# topboard-v1.net
KiCad netlist of a schematic drawn in EAGLE
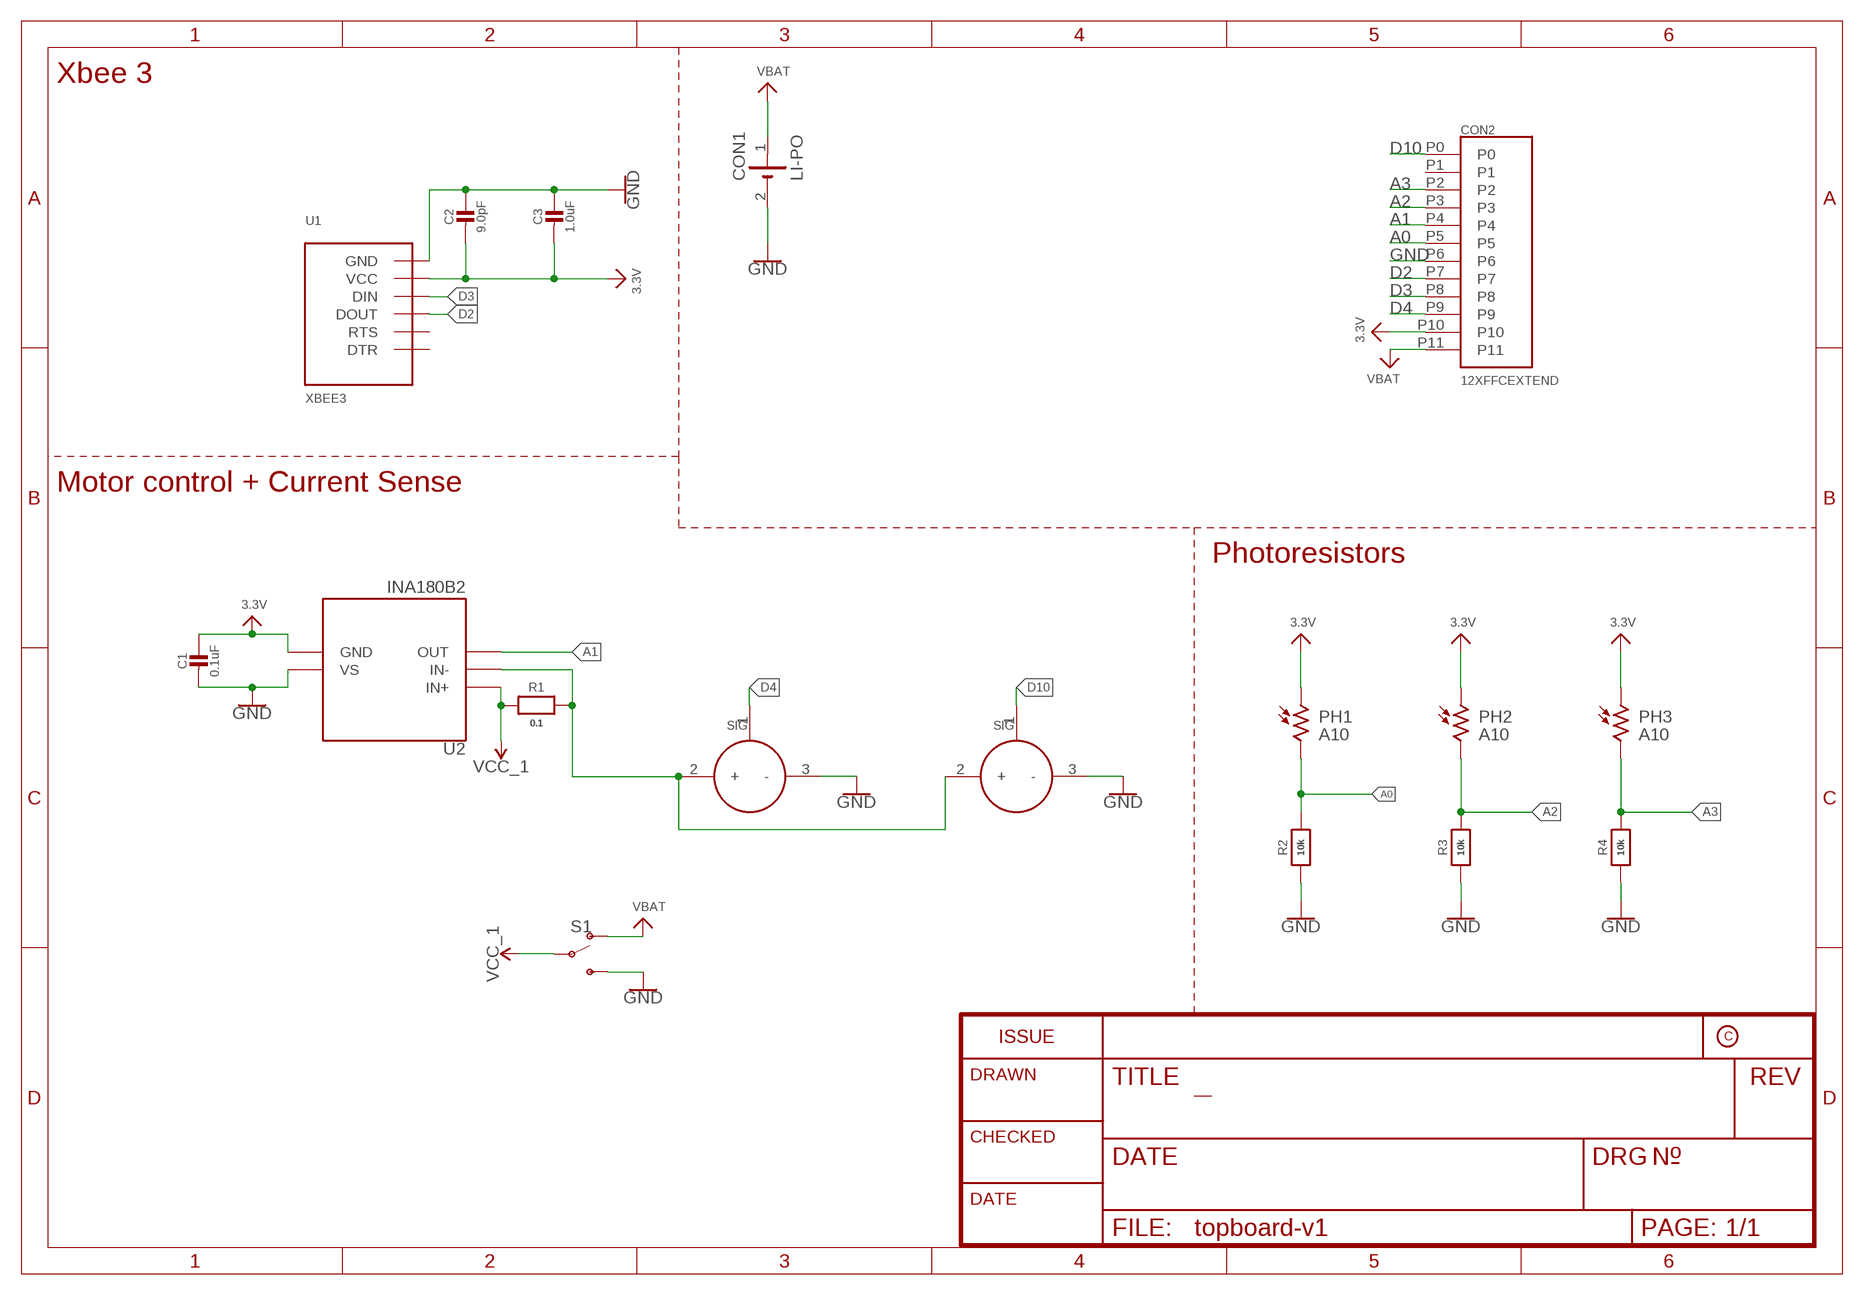
[diagram p0: schematic, sheet 1]

(export (version "E")
  (design (tool "Eeschema 10.0.6"))
  (components
    (comp (ref "C1")
      (value "0.1uF")
      (footprint "eagle-import:_0603MP")
      (libsource (lib "eagle-import") (part "CAP_CERAMIC_0603MP"))
    )
    (comp (ref "C2")
      (value "9.0pF")
      (footprint "eagle-import:_0603MP")
      (libsource (lib "eagle-import") (part "CAP_CERAMIC_0603MP"))
    )
    (comp (ref "C3")
      (value "1.0uF")
      (footprint "eagle-import:_0603MP")
      (libsource (lib "eagle-import") (part "CAP_CERAMIC_0603MP"))
    )
    (comp (ref "CON1")
      (value "LI-PO")
      (footprint "eagle-import:1X02_BATT")
      (libsource (lib "eagle-import") (part "LI-PO"))
    )
    (comp (ref "CON2")
      (value "12XFFCEXTEND")
      (footprint "eagle-import:15166-0117_XTEND")
      (libsource (lib "eagle-import") (part "12XFFCEXTEND"))
    )
    (comp (ref "M1")
      (value "SERVO")
      (footprint "eagle-import:1X03_SERVO")
      (libsource (lib "eagle-import") (part "SERVO"))
    )
    (comp (ref "M2")
      (value "SERVO")
      (footprint "eagle-import:1X03_SERVO")
      (libsource (lib "eagle-import") (part "SERVO"))
    )
    (comp (ref "PH1")
      (value "A10")
      (footprint "eagle-import:PHOTORESISTOR")
      (libsource (lib "eagle-import") (part "A10"))
    )
    (comp (ref "PH2")
      (value "A10")
      (footprint "eagle-import:PHOTORESISTOR")
      (libsource (lib "eagle-import") (part "A10"))
    )
    (comp (ref "PH3")
      (value "A10")
      (footprint "eagle-import:PHOTORESISTOR")
      (libsource (lib "eagle-import") (part "A10"))
    )
    (comp (ref "R1")
      (value "0.1")
      (footprint "eagle-import:_0603MP")
      (libsource (lib "eagle-import") (part "RESISTOR_0603MP"))
    )
    (comp (ref "R2")
      (value "10k")
      (footprint "eagle-import:_0603MP")
      (libsource (lib "eagle-import") (part "RESISTOR_0603MP"))
    )
    (comp (ref "R3")
      (value "10k")
      (footprint "eagle-import:_0603MP")
      (libsource (lib "eagle-import") (part "RESISTOR_0603MP"))
    )
    (comp (ref "R4")
      (value "10k")
      (footprint "eagle-import:_0603MP")
      (libsource (lib "eagle-import") (part "RESISTOR_0603MP"))
    )
    (comp (ref "S1")
      (value "SWITCH-SPDT-SMD-RIGHT-ANGLE")
      (footprint "eagle-import:SWITCH_SPST_SMD_A")
      (libsource (lib "eagle-import") (part "SWITCH-SPDT-SMD-RIGHT-ANGLE"))
    )
    (comp (ref "U1")
      (value "XBEE3")
      (footprint "eagle-import:XBEE3_MICRO")
      (libsource (lib "eagle-import") (part "XBEE3"))
    )
    (comp (ref "U2")
      (value "INA180B2")
      (footprint "eagle-import:SOT23-5")
      (libsource (lib "eagle-import") (part "INA180B2"))
    )
  )
  (nets
    (net (code "1") (name "3.3V") (class "Default")
      (node (ref "C1") (pin "1") (pinfunction "1_1") (pintype "passive"))
      (node (ref "C2") (pin "2") (pinfunction "2_2") (pintype "passive"))
      (node (ref "C3") (pin "2") (pinfunction "2_2") (pintype "passive"))
      (node (ref "CON2") (pin "P10") (pinfunction "P10_P10") (pintype "bidirectional"))
      (node (ref "PH1") (pin "1") (pinfunction "1_1") (pintype "passive"))
      (node (ref "PH2") (pin "1") (pinfunction "1_1") (pintype "passive"))
      (node (ref "PH3") (pin "1") (pinfunction "1_1") (pintype "passive"))
      (node (ref "U1") (pin "VCC") (pinfunction "VCC_VCC") (pintype "bidirectional"))
      (node (ref "U2") (pin "2") (pinfunction "GND_2") (pintype "bidirectional"))
    )
    (net (code "2") (name "A0") (class "Default")
      (node (ref "CON2") (pin "P5") (pinfunction "P5_P5") (pintype "bidirectional"))
      (node (ref "PH1") (pin "2") (pinfunction "2_2") (pintype "passive"))
      (node (ref "R2") (pin "2") (pinfunction "2_2") (pintype "passive"))
    )
    (net (code "3") (name "A1") (class "Default")
      (node (ref "CON2") (pin "P4") (pinfunction "P4_P4") (pintype "bidirectional"))
      (node (ref "U2") (pin "4") (pinfunction "OUT_4") (pintype "bidirectional"))
    )
    (net (code "4") (name "A2") (class "Default")
      (node (ref "CON2") (pin "P3") (pinfunction "P3_P3") (pintype "bidirectional"))
      (node (ref "PH2") (pin "2") (pinfunction "2_2") (pintype "passive"))
      (node (ref "R3") (pin "2") (pinfunction "2_2") (pintype "passive"))
    )
    (net (code "5") (name "A3") (class "Default")
      (node (ref "CON2") (pin "P2") (pinfunction "P2_P2") (pintype "bidirectional"))
      (node (ref "PH3") (pin "2") (pinfunction "2_2") (pintype "passive"))
      (node (ref "R4") (pin "2") (pinfunction "2_2") (pintype "passive"))
    )
    (net (code "6") (name "D2") (class "Default")
      (node (ref "CON2") (pin "P7") (pinfunction "P7_P7") (pintype "bidirectional"))
      (node (ref "U1") (pin "DOUT/DIO13") (pinfunction "DOUT_DOUT/DIO13") (pintype "bidirectional"))
    )
    (net (code "7") (name "D3") (class "Default")
      (node (ref "CON2") (pin "P8") (pinfunction "P8_P8") (pintype "bidirectional"))
      (node (ref "U1") (pin "DIN/CONFIG/DIO14") (pinfunction "DIN_DIN/CONFIG/DIO14") (pintype "bidirectional"))
    )
    (net (code "8") (name "D4") (class "Default")
      (node (ref "CON2") (pin "P9") (pinfunction "P9_P9") (pintype "bidirectional"))
      (node (ref "M1") (pin "1") (pinfunction "SIG_1") (pintype "bidirectional"))
    )
    (net (code "9") (name "D10") (class "Default")
      (node (ref "CON2") (pin "P0") (pinfunction "P0_P0") (pintype "bidirectional"))
      (node (ref "M2") (pin "1") (pinfunction "SIG_1") (pintype "bidirectional"))
    )
    (net (code "10") (name "GND") (class "Default")
      (node (ref "C1") (pin "2") (pinfunction "2_2") (pintype "passive"))
      (node (ref "C2") (pin "1") (pinfunction "1_1") (pintype "passive"))
      (node (ref "C3") (pin "1") (pinfunction "1_1") (pintype "passive"))
      (node (ref "CON1") (pin "2") (pinfunction "-_2") (pintype "passive"))
      (node (ref "CON2") (pin "P6") (pinfunction "P6_P6") (pintype "bidirectional"))
      (node (ref "M1") (pin "3") (pinfunction "-_3") (pintype "bidirectional"))
      (node (ref "M2") (pin "3") (pinfunction "-_3") (pintype "bidirectional"))
      (node (ref "R2") (pin "1") (pinfunction "1_1") (pintype "passive"))
      (node (ref "R3") (pin "1") (pinfunction "1_1") (pintype "passive"))
      (node (ref "R4") (pin "1") (pinfunction "1_1") (pintype "passive"))
      (node (ref "S1") (pin "3") (pinfunction "S_3") (pintype "passive"))
      (node (ref "U1") (pin "GND1") (pinfunction "GND_GND1") (pintype "bidirectional"))
      (node (ref "U1") (pin "GND2") (pinfunction "GND_GND2") (pintype "bidirectional"))
      (node (ref "U1") (pin "GND3") (pinfunction "GND_GND3") (pintype "bidirectional"))
      (node (ref "U1") (pin "GND4") (pinfunction "GND_GND4") (pintype "bidirectional"))
      (node (ref "U1") (pin "GND5") (pinfunction "GND_GND5") (pintype "bidirectional"))
      (node (ref "U1") (pin "GND6") (pinfunction "GND_GND6") (pintype "bidirectional"))
      (node (ref "U2") (pin "5") (pinfunction "VS_5") (pintype "bidirectional"))
    )
    (net (code "11") (name "Net-(M1-+)") (class "Default")
      (node (ref "M1") (pin "2") (pinfunction "+_2") (pintype "bidirectional"))
      (node (ref "M2") (pin "2") (pinfunction "+_2") (pintype "bidirectional"))
      (node (ref "R1") (pin "2") (pinfunction "2_2") (pintype "passive"))
      (node (ref "U2") (pin "3") (pinfunction "IN-_3") (pintype "bidirectional"))
    )
    (net (code "12") (name "VBAT") (class "Default")
      (node (ref "CON1") (pin "1") (pinfunction "+_1") (pintype "passive"))
      (node (ref "CON2") (pin "P11") (pinfunction "P11_P11") (pintype "bidirectional"))
      (node (ref "S1") (pin "1") (pinfunction "O_1") (pintype "passive"))
    )
    (net (code "13") (name "VCC_1") (class "Default")
      (node (ref "R1") (pin "1") (pinfunction "1_1") (pintype "passive"))
      (node (ref "S1") (pin "2") (pinfunction "P_2") (pintype "passive"))
      (node (ref "U2") (pin "1") (pinfunction "IN+_1") (pintype "bidirectional"))
    )
    (net (code "14") (name "unconnected-(CON2-PadP1)") (class "Default")
      (node (ref "CON2") (pin "P1") (pinfunction "P1_P1") (pintype "bidirectional"))
    )
    (net (code "15") (name "unconnected-(U1-DTR-PadDTR{slash}SLEEP_RQ{slash}DIO8)") (class "Default")
      (node (ref "U1") (pin "DTR/SLEEP_RQ/DIO8") (pinfunction "DTR_DTR/SLEEP_RQ/DIO8") (pintype "bidirectional"))
    )
    (net (code "16") (name "unconnected-(U1-RTS-PadRTS{slash}DIO6)") (class "Default")
      (node (ref "U1") (pin "RTS/DIO6") (pinfunction "RTS_RTS/DIO6") (pintype "bidirectional"))
    )
  )
)
